# connect_4_v1.net
KiCad netlist of a schematic drawn in EasyEDA
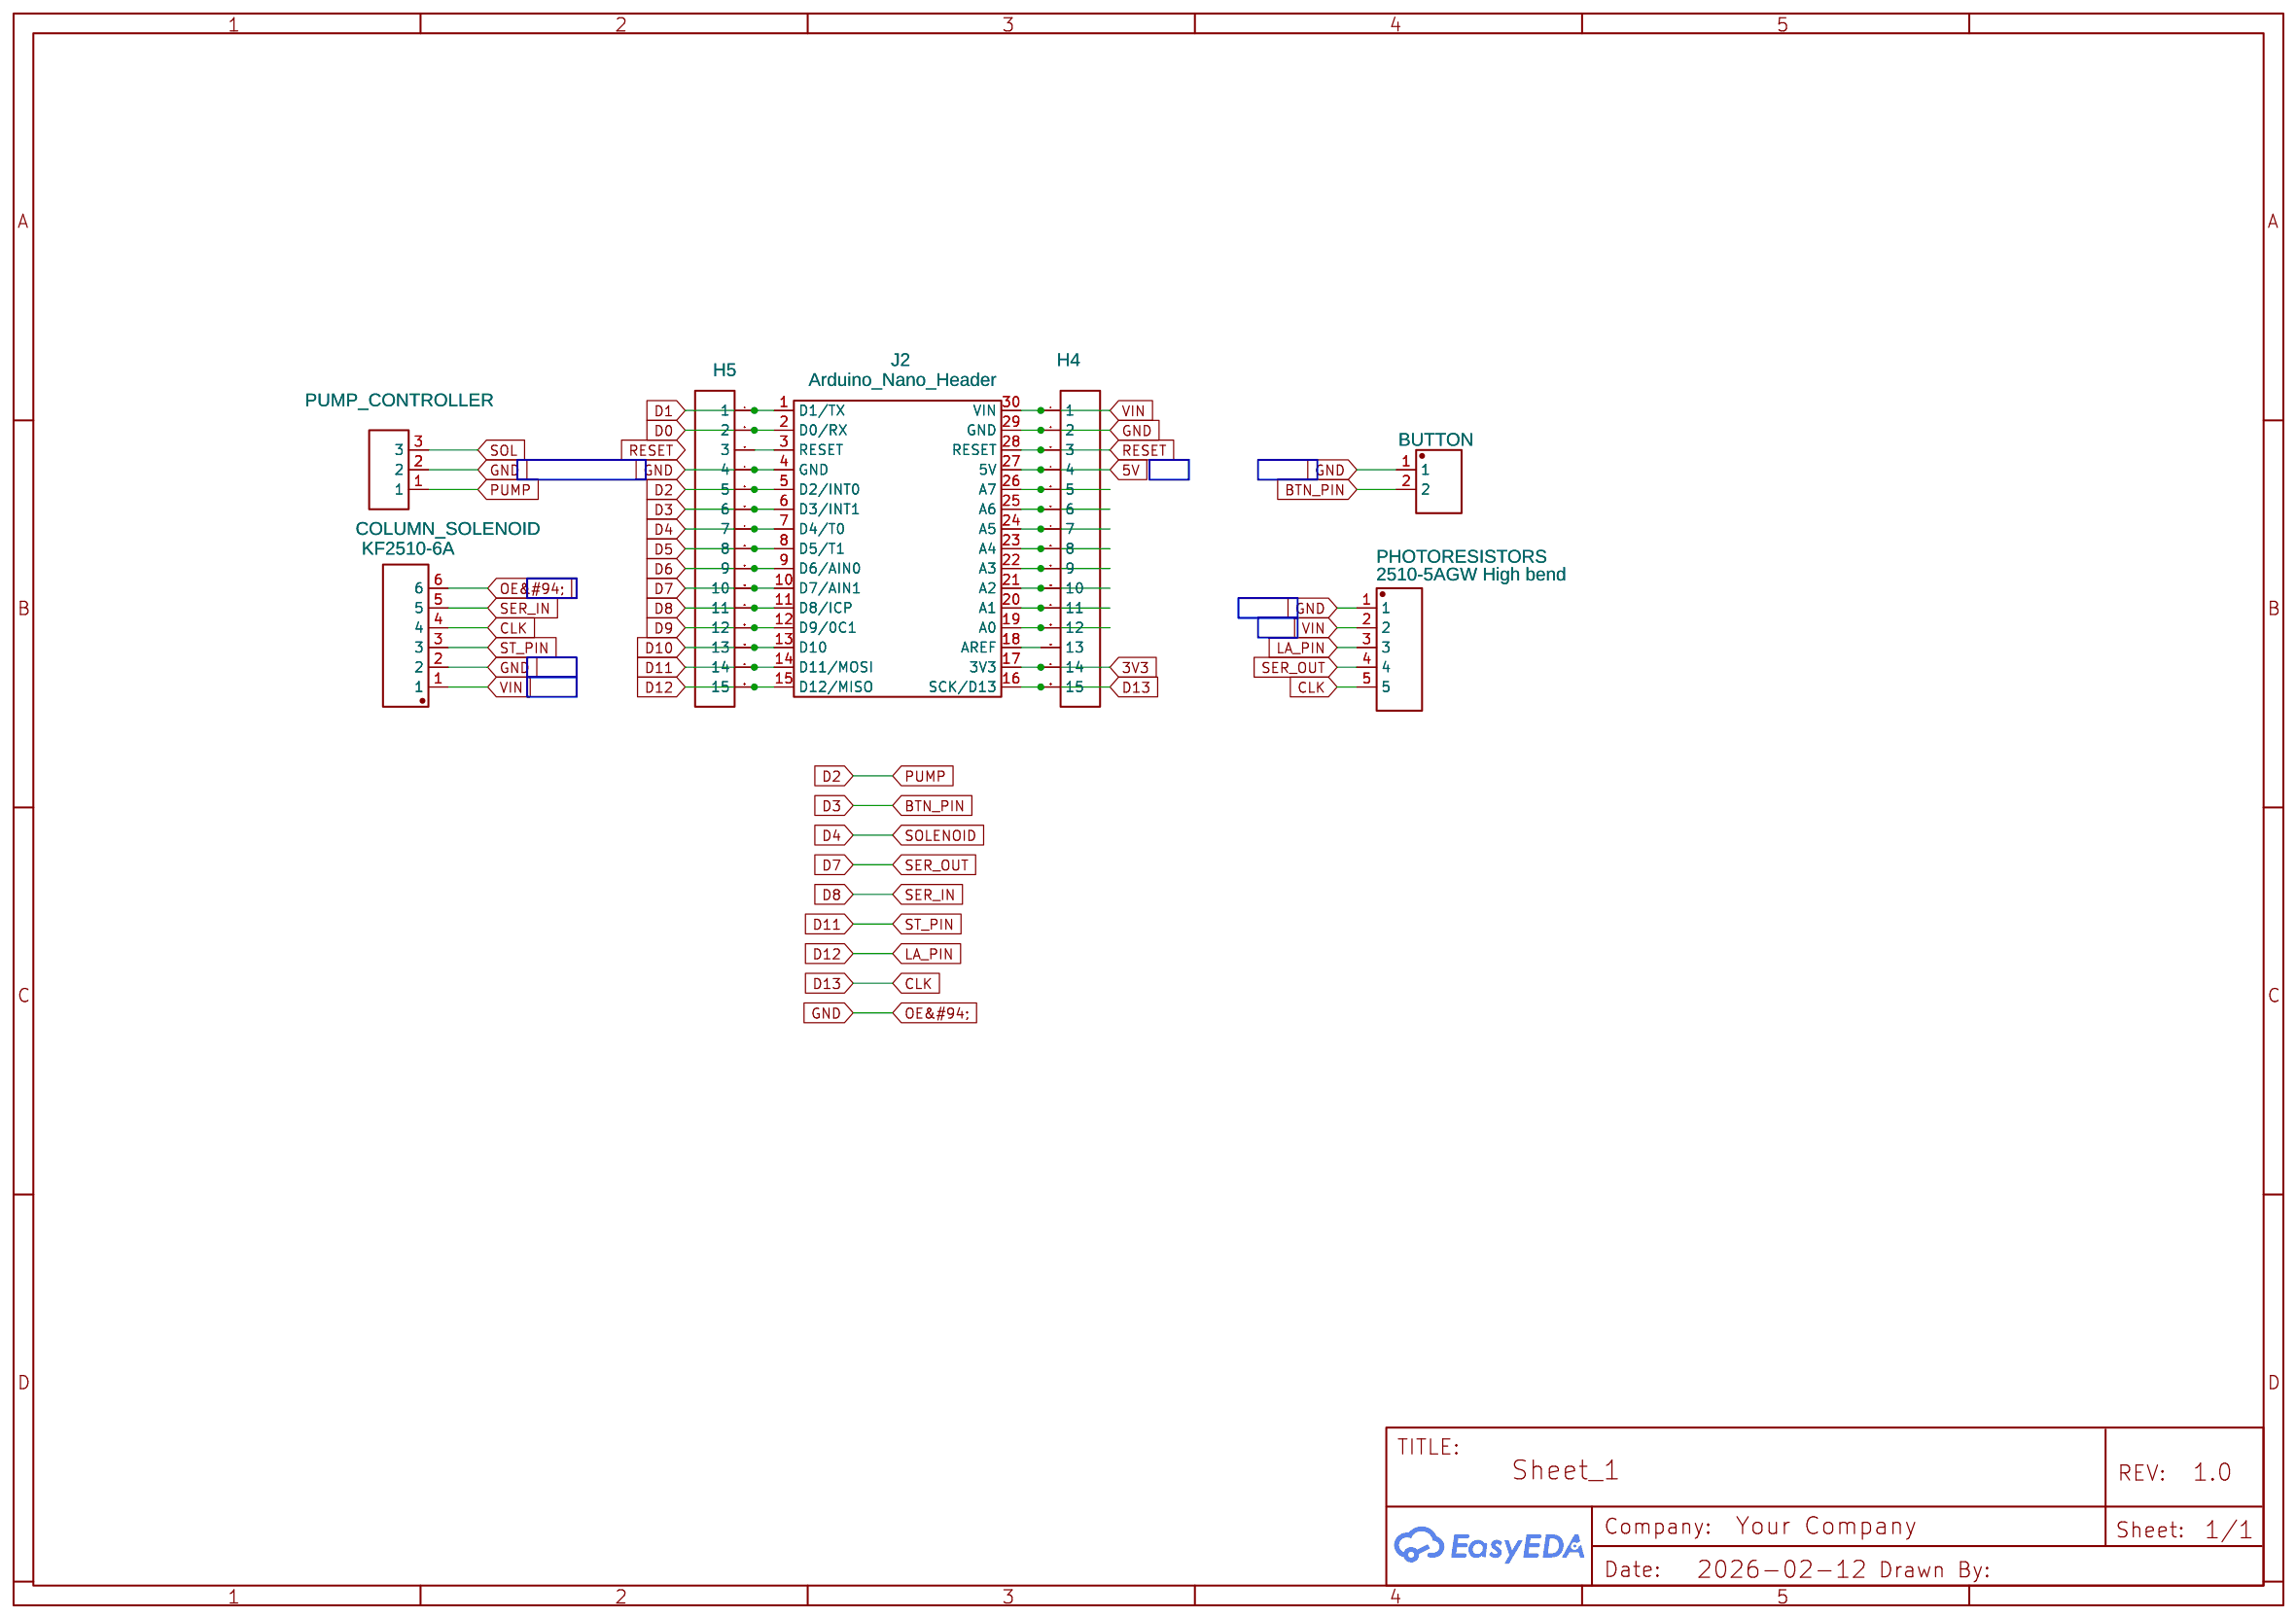
[diagram p0: schematic sheet]

(export (version "E")
  (design (tool "Eeschema 10.0.6"))
  (components
    (comp (ref "COLUMN_SOLENOID")
      (value "KF2510-6A")
      (fields (field (name "Manufacturer Part") "KF2510-6A针座"))
      (libsource (lib "") (part "KF2510-6A"))
    )
    (comp (ref "D3")
      (value "BUTTON")
      (fields (field (name "Manufacturer Part") "KF2510-2A") (field (name "Manufacturer") "BOOMELE"))
      (libsource (lib "") (part "KF2510-2A"))
    )
    (comp (ref "H4") (value "HDR-F-2.54_1x15") (libsource (lib "") (part "HDR-F-2.54_1x15")))
    (comp (ref "H5") (value "HDR-F-2.54_1x15") (libsource (lib "") (part "HDR-F-2.54_1x15_1")))
    (comp (ref "J2") (value "Arduino_Nano_Header") (libsource (lib "") (part "Arduino_Nano_Header")))
    (comp (ref "PHOTORESISTORS")
      (value "2510-5AGW High bend")
      (fields (field (name "Manufacturer Part") "2510-5A高弯") (field (name "Manufacturer") "BOOMELE(博穆精密)"))
      (libsource (lib "") (part "2510-5AGW High bend"))
    )
    (comp (ref "PUMP_CONTROLLER") (value "FK2510") (libsource (lib "") (part "kf2510_3A")))
  )
  (nets
    (net (code "1") (name "3V3") (class "Default")
      (node (ref "H4") (pin "14") (pinfunction "14_14") (pintype "unspecified"))
      (node (ref "J2") (pin "17") (pinfunction "3V3_17") (pintype "unspecified"))
    )
    (net (code "2") (name "5V") (class "Default")
      (node (ref "H4") (pin "4") (pinfunction "4_4") (pintype "unspecified"))
      (node (ref "J2") (pin "27") (pinfunction "5V_27") (pintype "unspecified"))
    )
    (net (code "3") (name "BTN_PIN") (class "Default")
      (node (ref "D3") (pin "2") (pinfunction "2_2") (pintype "unspecified"))
      (node (ref "H5") (pin "6") (pinfunction "6_6") (pintype "unspecified"))
      (node (ref "J2") (pin "6") (pinfunction "D3/INT1_6") (pintype "unspecified"))
    )
    (net (code "4") (name "CLK") (class "Default")
      (node (ref "COLUMN_SOLENOID") (pin "4") (pinfunction "4_4") (pintype "unspecified"))
      (node (ref "H4") (pin "15") (pinfunction "15_15") (pintype "unspecified"))
      (node (ref "J2") (pin "16") (pinfunction "SCK/D13_16") (pintype "unspecified"))
      (node (ref "PHOTORESISTORS") (pin "5") (pinfunction "5_5") (pintype "unspecified"))
    )
    (net (code "5") (name "D0") (class "Default")
      (node (ref "H5") (pin "2") (pinfunction "2_2") (pintype "unspecified"))
      (node (ref "J2") (pin "2") (pinfunction "D0/RX_2") (pintype "unspecified"))
    )
    (net (code "6") (name "D1") (class "Default")
      (node (ref "H5") (pin "1") (pinfunction "1_1") (pintype "unspecified"))
      (node (ref "J2") (pin "1") (pinfunction "D1/TX_1") (pintype "unspecified"))
    )
    (net (code "7") (name "D2") (class "Default")
      (node (ref "H5") (pin "5") (pinfunction "5_5") (pintype "unspecified"))
      (node (ref "J2") (pin "5") (pinfunction "D2/INT0_5") (pintype "unspecified"))
      (node (ref "PUMP_CONTROLLER") (pin "1") (pinfunction "1_1") (pintype "unspecified"))
    )
    (net (code "8") (name "D4") (class "Default")
      (node (ref "H5") (pin "7") (pinfunction "7_7") (pintype "unspecified"))
      (node (ref "J2") (pin "7") (pinfunction "D4/T0_7") (pintype "unspecified"))
    )
    (net (code "9") (name "D5") (class "Default")
      (node (ref "H5") (pin "8") (pinfunction "8_8") (pintype "unspecified"))
      (node (ref "J2") (pin "8") (pinfunction "D5/T1_8") (pintype "unspecified"))
    )
    (net (code "10") (name "D6") (class "Default")
      (node (ref "H5") (pin "9") (pinfunction "9_9") (pintype "unspecified"))
      (node (ref "J2") (pin "9") (pinfunction "D6/AIN0_9") (pintype "unspecified"))
    )
    (net (code "11") (name "D7") (class "Default")
      (node (ref "H5") (pin "10") (pinfunction "10_10") (pintype "unspecified"))
      (node (ref "J2") (pin "10") (pinfunction "D7/AIN1_10") (pintype "unspecified"))
      (node (ref "PHOTORESISTORS") (pin "4") (pinfunction "4_4") (pintype "unspecified"))
    )
    (net (code "12") (name "D8") (class "Default")
      (node (ref "COLUMN_SOLENOID") (pin "5") (pinfunction "5_5") (pintype "unspecified"))
      (node (ref "H5") (pin "11") (pinfunction "11_11") (pintype "unspecified"))
      (node (ref "J2") (pin "11") (pinfunction "D8/ICP_11") (pintype "unspecified"))
    )
    (net (code "13") (name "D9") (class "Default")
      (node (ref "H5") (pin "12") (pinfunction "12_12") (pintype "unspecified"))
      (node (ref "J2") (pin "12") (pinfunction "D9/0C1_12") (pintype "unspecified"))
    )
    (net (code "14") (name "D10") (class "Default")
      (node (ref "H5") (pin "13") (pinfunction "13_13") (pintype "unspecified"))
      (node (ref "J2") (pin "13") (pinfunction "D10_13") (pintype "unspecified"))
    )
    (net (code "15") (name "D11") (class "Default")
      (node (ref "COLUMN_SOLENOID") (pin "3") (pinfunction "3_3") (pintype "unspecified"))
      (node (ref "H5") (pin "14") (pinfunction "14_14") (pintype "unspecified"))
      (node (ref "J2") (pin "14") (pinfunction "D11/MOSI_14") (pintype "unspecified"))
    )
    (net (code "16") (name "D12") (class "Default")
      (node (ref "H5") (pin "15") (pinfunction "15_15") (pintype "unspecified"))
      (node (ref "J2") (pin "15") (pinfunction "D12/MISO_15") (pintype "unspecified"))
      (node (ref "PHOTORESISTORS") (pin "3") (pinfunction "3_3") (pintype "unspecified"))
    )
    (net (code "17") (name "GND") (class "Default")
      (node (ref "COLUMN_SOLENOID") (pin "2") (pinfunction "2_2") (pintype "unspecified"))
      (node (ref "COLUMN_SOLENOID") (pin "6") (pinfunction "6_6") (pintype "unspecified"))
      (node (ref "D3") (pin "1") (pinfunction "1_1") (pintype "unspecified"))
      (node (ref "H4") (pin "2") (pinfunction "2_2") (pintype "unspecified"))
      (node (ref "H5") (pin "4") (pinfunction "4_4") (pintype "unspecified"))
      (node (ref "J2") (pin "29") (pinfunction "GND_29") (pintype "unspecified"))
      (node (ref "J2") (pin "4") (pinfunction "GND_4") (pintype "unspecified"))
      (node (ref "PHOTORESISTORS") (pin "1") (pinfunction "1_1") (pintype "unspecified"))
      (node (ref "PUMP_CONTROLLER") (pin "2") (pinfunction "2_2") (pintype "unspecified"))
    )
    (net (code "18") (name "Net-(H5-Pad3)") (class "Default")
      (node (ref "H5") (pin "3") (pinfunction "3_3") (pintype "unspecified"))
      (node (ref "J2") (pin "3") (pinfunction "RESET_3") (pintype "unspecified"))
    )
    (net (code "19") (name "Net-(J2-A0)") (class "Default")
      (node (ref "H4") (pin "12") (pinfunction "12_12") (pintype "unspecified"))
      (node (ref "J2") (pin "19") (pinfunction "A0_19") (pintype "unspecified"))
    )
    (net (code "20") (name "Net-(J2-A1)") (class "Default")
      (node (ref "H4") (pin "11") (pinfunction "11_11") (pintype "unspecified"))
      (node (ref "J2") (pin "20") (pinfunction "A1_20") (pintype "unspecified"))
    )
    (net (code "21") (name "Net-(J2-A2)") (class "Default")
      (node (ref "H4") (pin "10") (pinfunction "10_10") (pintype "unspecified"))
      (node (ref "J2") (pin "21") (pinfunction "A2_21") (pintype "unspecified"))
    )
    (net (code "22") (name "Net-(J2-A3)") (class "Default")
      (node (ref "H4") (pin "9") (pinfunction "9_9") (pintype "unspecified"))
      (node (ref "J2") (pin "22") (pinfunction "A3_22") (pintype "unspecified"))
    )
    (net (code "23") (name "Net-(J2-A4)") (class "Default")
      (node (ref "H4") (pin "8") (pinfunction "8_8") (pintype "unspecified"))
      (node (ref "J2") (pin "23") (pinfunction "A4_23") (pintype "unspecified"))
    )
    (net (code "24") (name "Net-(J2-A5)") (class "Default")
      (node (ref "H4") (pin "7") (pinfunction "7_7") (pintype "unspecified"))
      (node (ref "J2") (pin "24") (pinfunction "A5_24") (pintype "unspecified"))
    )
    (net (code "25") (name "Net-(J2-A6)") (class "Default")
      (node (ref "H4") (pin "6") (pinfunction "6_6") (pintype "unspecified"))
      (node (ref "J2") (pin "25") (pinfunction "A6_25") (pintype "unspecified"))
    )
    (net (code "26") (name "Net-(J2-A7)") (class "Default")
      (node (ref "H4") (pin "5") (pinfunction "5_5") (pintype "unspecified"))
      (node (ref "J2") (pin "26") (pinfunction "A7_26") (pintype "unspecified"))
    )
    (net (code "27") (name "Net-(J2-AREF)") (class "Default")
      (node (ref "H4") (pin "13") (pinfunction "13_13") (pintype "unspecified"))
      (node (ref "J2") (pin "18") (pinfunction "AREF_18") (pintype "unspecified"))
    )
    (net (code "28") (name "RESET") (class "Default")
      (node (ref "H4") (pin "3") (pinfunction "3_3") (pintype "unspecified"))
      (node (ref "J2") (pin "28") (pinfunction "RESET_28") (pintype "unspecified"))
    )
    (net (code "29") (name "SOL") (class "Default")
      (node (ref "PUMP_CONTROLLER") (pin "3") (pinfunction "3_3") (pintype "unspecified"))
    )
    (net (code "30") (name "VIN") (class "Default")
      (node (ref "COLUMN_SOLENOID") (pin "1") (pinfunction "1_1") (pintype "unspecified"))
      (node (ref "H4") (pin "1") (pinfunction "1_1") (pintype "unspecified"))
      (node (ref "J2") (pin "30") (pinfunction "VIN_30") (pintype "unspecified"))
      (node (ref "PHOTORESISTORS") (pin "2") (pinfunction "2_2") (pintype "unspecified"))
    )
  )
)
